# connector.net
KiCad netlist of a schematic drawn in Altium Designer
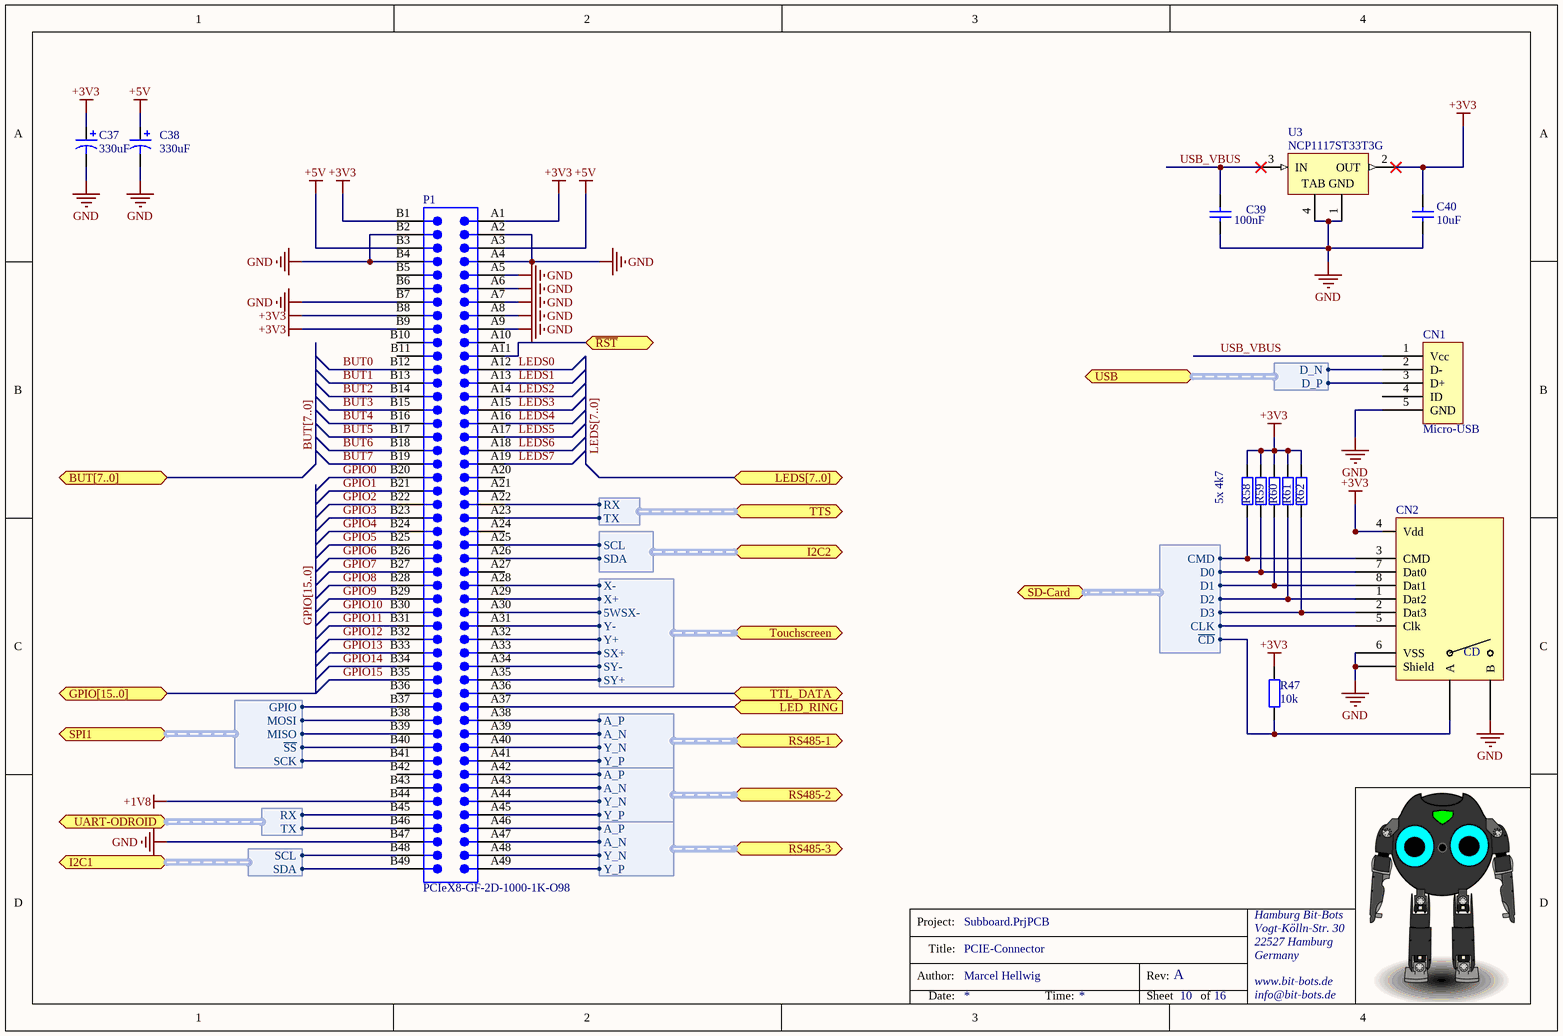
[diagram p0: connector.SchDoc]

(export (version "E")
  (design (tool "Eeschema 10.0.6"))
  (components
    (comp (ref "C37")
      (value "330uF")
      (footprint "Cap 10mm")
      (description "Polarized Capacitor (Radial)")
      (fields
        (field (name "MANUFACTURER") "PANASONIC ELECTRONIC COMPONENTS")
        (field (name "MANUFACTURER PART NUMBER") "EEE1VA331UAP")
        (field (name "PUBLISHER") "Altium Limited")
      )
      (libsource (lib "Miscellaneous Devices") (part "Cap Pol1"))
    )
    (comp (ref "C38")
      (value "330uF")
      (footprint "Cap 10mm")
      (description "Polarized Capacitor (Radial)")
      (fields
        (field (name "MANUFACTURER") "PANASONIC ELECTRONIC COMPONENTS")
        (field (name "MANUFACTURER PART NUMBER") "EEE1VA331UAP")
        (field (name "PUBLISHER") "Altium Limited")
      )
      (libsource (lib "Miscellaneous Devices") (part "Cap Pol1"))
    )
    (comp (ref "C39")
      (value "100nF")
      (footprint "C2012")
      (description "Capacitor")
      (fields
        (field (name "MANUFACTURER") "MULTICOMP")
        (field (name "MANUFACTURER PART NUMBER") "MC0805B104K500CT")
        (field (name "PUBLISHER") "Altium Limited")
      )
      (libsource (lib "Miscellaneous Devices") (part "Cap"))
    )
    (comp (ref "C40")
      (value "10uF")
      (footprint "C2012")
      (description "Capacitor")
      (fields
        (field (name "MANUFACTURER") "MULTICOMP")
        (field (name "MANUFACTURER PART NUMBER") "MC0805X106K250CT")
        (field (name "PUBLISHER") "Altium Limited")
      )
      (libsource (lib "Miscellaneous Devices") (part "Cap"))
    )
    (comp (ref "CN1")
      (value "Micro-USB")
      (footprint "USB-MicroB")
      (fields (field (name "MANUFACTURER") "Molex") (field (name "MANUFACTURER PART NUMBER") "105017-0001"))
      (libsource (lib "bitbots") (part "USB-MicroB"))
    )
    (comp (ref "CN2")
      (value "microSD")
      (footprint "Microsd")
      (description "Micro SD Card Connector")
      (libsource (lib "bitbots") (part "microSD"))
    )
    (comp (ref "P1")
      (value "PCIeX8-GF-2D-1000-1K-O98")
      (footprint "PCIeX8-GF-2D-1000-1K-O98")
      (description "Golden finger, PCIeX8, Dual, Opposite, Pitch 1mm, 98-Position")
      (fields (field (name "PUBLISHER") "Altium"))
      (libsource (lib "Altium Content Vault") (part "CMP-0001-00032-2"))
    )
    (comp (ref "R47")
      (value "10k")
      (footprint "R2012")
      (description "Resistor")
      (fields
        (field (name "MANUFACTURER") "MULTICOMP")
        (field (name "MANUFACTURER PART NUMBER") "MC01W0805110K")
        (field (name "PUBLISHER") "Altium Limited")
      )
      (libsource (lib "") (part "Res2_1"))
    )
    (comp (ref "R58")
      (value "4k7")
      (footprint "R2012")
      (description "Resistor")
      (fields
        (field (name "MANUFACTURER") "MULTICOMP")
        (field (name "MANUFACTURER PART NUMBER") "MC01W080514K7")
        (field (name "PUBLISHER") "Altium Limited")
      )
      (libsource (lib "Miscellaneous Devices") (part "Res2"))
    )
    (comp (ref "R59")
      (value "4k7")
      (footprint "R2012")
      (description "Resistor")
      (fields
        (field (name "MANUFACTURER") "MULTICOMP")
        (field (name "MANUFACTURER PART NUMBER") "MC01W080514K7")
        (field (name "PUBLISHER") "Altium Limited")
      )
      (libsource (lib "Miscellaneous Devices") (part "Res2"))
    )
    (comp (ref "R60")
      (value "4k7")
      (footprint "R2012")
      (description "Resistor")
      (fields
        (field (name "MANUFACTURER") "MULTICOMP")
        (field (name "MANUFACTURER PART NUMBER") "MC01W080514K7")
        (field (name "PUBLISHER") "Altium Limited")
      )
      (libsource (lib "Miscellaneous Devices") (part "Res2"))
    )
    (comp (ref "R61")
      (value "4k7")
      (footprint "R2012")
      (description "Resistor")
      (fields
        (field (name "MANUFACTURER") "MULTICOMP")
        (field (name "MANUFACTURER PART NUMBER") "MC01W080514K7")
        (field (name "PUBLISHER") "Altium Limited")
      )
      (libsource (lib "Miscellaneous Devices") (part "Res2"))
    )
    (comp (ref "R62")
      (value "4k7")
      (footprint "R2012")
      (description "Resistor")
      (fields
        (field (name "MANUFACTURER") "MULTICOMP")
        (field (name "MANUFACTURER PART NUMBER") "MC01W080514K7")
        (field (name "PUBLISHER") "Altium Limited")
      )
      (libsource (lib "Miscellaneous Devices") (part "Res2"))
    )
    (comp (ref "U3")
      (value "NCP1117ST33T3G")
      (footprint "ONSC-SOT-223_L")
      (fields (field (name "PARTNUMBER") "NCP1117ST50T3G") (field (name "MANUFACTURER") "ON Semiconductor"))
      (libsource (lib "Altium Content Vault") (part "CMP-0592-00001-2"))
    )
  )
  (nets
    (net (code "8") (name "+1V8") (class "Default")
      (node (ref "P1") (pin "B44") (pinfunction "B44_B44") (pintype "passive"))
    )
    (net (code "9") (name "+3V3") (class "Default")
      (node (ref "C37") (pin "1") (pinfunction "1_1") (pintype "passive"))
      (node (ref "C40") (pin "2") (pinfunction "2_2") (pintype "passive"))
      (node (ref "CN2") (pin "4") (pinfunction "Vdd_4") (pintype "passive"))
      (node (ref "P1") (pin "A1") (pinfunction "A1_A1") (pintype "passive"))
      (node (ref "P1") (pin "B1") (pinfunction "B1_B1") (pintype "passive"))
      (node (ref "P1") (pin "B8") (pinfunction "B8_B8") (pintype "passive"))
      (node (ref "P1") (pin "B9") (pinfunction "B9_B9") (pintype "passive"))
      (node (ref "R47") (pin "2") (pinfunction "2_2") (pintype "passive"))
      (node (ref "R58") (pin "1") (pinfunction "1_1") (pintype "passive"))
      (node (ref "R59") (pin "1") (pinfunction "1_1") (pintype "passive"))
      (node (ref "R60") (pin "1") (pinfunction "1_1") (pintype "passive"))
      (node (ref "R61") (pin "1") (pinfunction "1_1") (pintype "passive"))
      (node (ref "R62") (pin "1") (pinfunction "1_1") (pintype "passive"))
      (node (ref "U3") (pin "2") (pinfunction "OUT_2") (pintype "output"))
    )
    (net (code "10") (name "+5V") (class "Default")
      (node (ref "C38") (pin "1") (pinfunction "1_1") (pintype "passive"))
      (node (ref "P1") (pin "A3") (pinfunction "A3_A3") (pintype "passive"))
      (node (ref "P1") (pin "B3") (pinfunction "B3_B3") (pintype "passive"))
    )
    (net (code "11") (name "/5WSX-") (class "Default")
      (node (ref "P1") (pin "A30") (pinfunction "A30_A30") (pintype "passive"))
    )
    (net (code "12") (name "/BUT0") (class "Default")
      (node (ref "P1") (pin "B12") (pinfunction "B12_B12") (pintype "passive"))
    )
    (net (code "13") (name "/BUT1") (class "Default")
      (node (ref "P1") (pin "B13") (pinfunction "B13_B13") (pintype "passive"))
    )
    (net (code "14") (name "/BUT2") (class "Default")
      (node (ref "P1") (pin "B14") (pinfunction "B14_B14") (pintype "passive"))
    )
    (net (code "15") (name "/BUT3") (class "Default")
      (node (ref "P1") (pin "B15") (pinfunction "B15_B15") (pintype "passive"))
    )
    (net (code "16") (name "/BUT4") (class "Default")
      (node (ref "P1") (pin "B16") (pinfunction "B16_B16") (pintype "passive"))
    )
    (net (code "17") (name "/BUT5") (class "Default")
      (node (ref "P1") (pin "B17") (pinfunction "B17_B17") (pintype "passive"))
    )
    (net (code "18") (name "/BUT6") (class "Default")
      (node (ref "P1") (pin "B18") (pinfunction "B18_B18") (pintype "passive"))
    )
    (net (code "19") (name "/BUT7") (class "Default")
      (node (ref "P1") (pin "B19") (pinfunction "B19_B19") (pintype "passive"))
    )
    (net (code "21") (name "/CLK") (class "Default")
      (node (ref "CN2") (pin "5") (pinfunction "Clk_5") (pintype "passive"))
    )
    (net (code "22") (name "/CMD") (class "Default")
      (node (ref "CN2") (pin "3") (pinfunction "CMD_3") (pintype "passive"))
      (node (ref "R58") (pin "2") (pinfunction "2_2") (pintype "passive"))
    )
    (net (code "23") (name "/D0") (class "Default")
      (node (ref "CN2") (pin "7") (pinfunction "Dat0_7") (pintype "passive"))
      (node (ref "R59") (pin "2") (pinfunction "2_2") (pintype "passive"))
    )
    (net (code "24") (name "/D1") (class "Default")
      (node (ref "CN2") (pin "8") (pinfunction "Dat1_8") (pintype "passive"))
      (node (ref "R60") (pin "2") (pinfunction "2_2") (pintype "passive"))
    )
    (net (code "25") (name "/D2") (class "Default")
      (node (ref "CN2") (pin "1") (pinfunction "Dat2_1") (pintype "passive"))
      (node (ref "R61") (pin "2") (pinfunction "2_2") (pintype "passive"))
    )
    (net (code "26") (name "/D3") (class "Default")
      (node (ref "CN2") (pin "2") (pinfunction "Dat3_2") (pintype "passive"))
      (node (ref "R62") (pin "2") (pinfunction "2_2") (pintype "passive"))
    )
    (net (code "27") (name "/D_N") (class "Default")
      (node (ref "CN1") (pin "2") (pinfunction "D-_2") (pintype "passive"))
    )
    (net (code "28") (name "/D_P") (class "Default")
      (node (ref "CN1") (pin "3") (pinfunction "D+_3") (pintype "passive"))
    )
    (net (code "29") (name "/GPIO") (class "Default")
      (node (ref "P1") (pin "B37") (pinfunction "B37_B37") (pintype "passive"))
    )
    (net (code "30") (name "/GPIO0") (class "Default")
      (node (ref "P1") (pin "B20") (pinfunction "B20_B20") (pintype "passive"))
    )
    (net (code "31") (name "/GPIO1") (class "Default")
      (node (ref "P1") (pin "B21") (pinfunction "B21_B21") (pintype "passive"))
    )
    (net (code "32") (name "/GPIO2") (class "Default")
      (node (ref "P1") (pin "B22") (pinfunction "B22_B22") (pintype "passive"))
    )
    (net (code "33") (name "/GPIO3") (class "Default")
      (node (ref "P1") (pin "B23") (pinfunction "B23_B23") (pintype "passive"))
    )
    (net (code "34") (name "/GPIO4") (class "Default")
      (node (ref "P1") (pin "B24") (pinfunction "B24_B24") (pintype "passive"))
    )
    (net (code "35") (name "/GPIO5") (class "Default")
      (node (ref "P1") (pin "B25") (pinfunction "B25_B25") (pintype "passive"))
    )
    (net (code "36") (name "/GPIO6") (class "Default")
      (node (ref "P1") (pin "B26") (pinfunction "B26_B26") (pintype "passive"))
    )
    (net (code "37") (name "/GPIO7") (class "Default")
      (node (ref "P1") (pin "B27") (pinfunction "B27_B27") (pintype "passive"))
    )
    (net (code "38") (name "/GPIO8") (class "Default")
      (node (ref "P1") (pin "B28") (pinfunction "B28_B28") (pintype "passive"))
    )
    (net (code "39") (name "/GPIO9") (class "Default")
      (node (ref "P1") (pin "B29") (pinfunction "B29_B29") (pintype "passive"))
    )
    (net (code "40") (name "/GPIO10") (class "Default")
      (node (ref "P1") (pin "B30") (pinfunction "B30_B30") (pintype "passive"))
    )
    (net (code "41") (name "/GPIO11") (class "Default")
      (node (ref "P1") (pin "B31") (pinfunction "B31_B31") (pintype "passive"))
    )
    (net (code "42") (name "/GPIO12") (class "Default")
      (node (ref "P1") (pin "B32") (pinfunction "B32_B32") (pintype "passive"))
    )
    (net (code "43") (name "/GPIO13") (class "Default")
      (node (ref "P1") (pin "B33") (pinfunction "B33_B33") (pintype "passive"))
    )
    (net (code "44") (name "/GPIO14") (class "Default")
      (node (ref "P1") (pin "B34") (pinfunction "B34_B34") (pintype "passive"))
    )
    (net (code "45") (name "/GPIO15") (class "Default")
      (node (ref "P1") (pin "B35") (pinfunction "B35_B35") (pintype "passive"))
    )
    (net (code "47") (name "/LEDS0") (class "Default")
      (node (ref "P1") (pin "A12") (pinfunction "A12_A12") (pintype "passive"))
    )
    (net (code "48") (name "/LEDS1") (class "Default")
      (node (ref "P1") (pin "A13") (pinfunction "A13_A13") (pintype "passive"))
    )
    (net (code "49") (name "/LEDS2") (class "Default")
      (node (ref "P1") (pin "A14") (pinfunction "A14_A14") (pintype "passive"))
    )
    (net (code "50") (name "/LEDS3") (class "Default")
      (node (ref "P1") (pin "A15") (pinfunction "A15_A15") (pintype "passive"))
    )
    (net (code "51") (name "/LEDS4") (class "Default")
      (node (ref "P1") (pin "A16") (pinfunction "A16_A16") (pintype "passive"))
    )
    (net (code "52") (name "/LEDS5") (class "Default")
      (node (ref "P1") (pin "A17") (pinfunction "A17_A17") (pintype "passive"))
    )
    (net (code "53") (name "/LEDS6") (class "Default")
      (node (ref "P1") (pin "A18") (pinfunction "A18_A18") (pintype "passive"))
    )
    (net (code "54") (name "/LEDS7") (class "Default")
      (node (ref "P1") (pin "A19") (pinfunction "A19_A19") (pintype "passive"))
    )
    (net (code "56") (name "/LED_RING") (class "Default")
      (node (ref "P1") (pin "A37") (pinfunction "A37_A37") (pintype "passive"))
    )
    (net (code "57") (name "/MISO") (class "Default")
      (node (ref "P1") (pin "B39") (pinfunction "B39_B39") (pintype "passive"))
    )
    (net (code "58") (name "/MOSI") (class "Default")
      (node (ref "P1") (pin "B38") (pinfunction "B38_B38") (pintype "passive"))
    )
    (net (code "59") (name "/RST") (class "Default")
      (node (ref "P1") (pin "A11") (pinfunction "A11_A11") (pintype "passive"))
    )
    (net (code "60") (name "/SCK") (class "Default")
      (node (ref "P1") (pin "B41") (pinfunction "B41_B41") (pintype "passive"))
    )
    (net (code "61") (name "/SX+") (class "Default")
      (node (ref "P1") (pin "A33") (pinfunction "A33_A33") (pintype "passive"))
    )
    (net (code "62") (name "/SY+") (class "Default")
      (node (ref "P1") (pin "A35") (pinfunction "A35_A35") (pintype "passive"))
    )
    (net (code "63") (name "/SY-") (class "Default")
      (node (ref "P1") (pin "A34") (pinfunction "A34_A34") (pintype "passive"))
    )
    (net (code "64") (name "/TTL_DATA") (class "Default")
      (node (ref "P1") (pin "A36") (pinfunction "A36_A36") (pintype "passive"))
    )
    (net (code "65") (name "/USB_VBUS") (class "Default")
      (node (ref "C39") (pin "2") (pinfunction "2_2") (pintype "passive"))
      (node (ref "CN1") (pin "1") (pinfunction "Vcc_1") (pintype "power_in"))
      (node (ref "U3") (pin "3") (pinfunction "IN_3") (pintype "input"))
    )
    (net (code "66") (name "/X+") (class "Default")
      (node (ref "P1") (pin "A29") (pinfunction "A29_A29") (pintype "passive"))
    )
    (net (code "67") (name "/X-") (class "Default")
      (node (ref "P1") (pin "A28") (pinfunction "A28_A28") (pintype "passive"))
    )
    (net (code "68") (name "/Y+") (class "Default")
      (node (ref "P1") (pin "A32") (pinfunction "A32_A32") (pintype "passive"))
    )
    (net (code "69") (name "/Y-") (class "Default")
      (node (ref "P1") (pin "A31") (pinfunction "A31_A31") (pintype "passive"))
    )
    (net (code "77") (name "/~{CD}") (class "Default")
      (node (ref "CN2") (pin "A") (pinfunction "A_A") (pintype "passive"))
      (node (ref "R47") (pin "1") (pinfunction "1_1") (pintype "passive"))
    )
    (net (code "78") (name "/~{SS}") (class "Default")
      (node (ref "P1") (pin "B40") (pinfunction "B40_B40") (pintype "passive"))
    )
    (net (code "79") (name "GND") (class "Default")
      (node (ref "C37") (pin "2") (pinfunction "2_2") (pintype "passive"))
      (node (ref "C38") (pin "2") (pinfunction "2_2") (pintype "passive"))
      (node (ref "C39") (pin "1") (pinfunction "1_1") (pintype "passive"))
      (node (ref "C40") (pin "1") (pinfunction "1_1") (pintype "passive"))
      (node (ref "CN1") (pin "5") (pinfunction "GND_5") (pintype "power_in"))
      (node (ref "CN2") (pin "6") (pinfunction "VSS_6") (pintype "passive"))
      (node (ref "CN2") (pin "B") (pinfunction "B_B") (pintype "passive"))
      (node (ref "CN2") (pin "sh") (pinfunction "Shield_sh") (pintype "passive"))
      (node (ref "P1") (pin "A2") (pinfunction "A2_A2") (pintype "passive"))
      (node (ref "P1") (pin "A4") (pinfunction "A4_A4") (pintype "passive"))
      (node (ref "P1") (pin "A5") (pinfunction "A5_A5") (pintype "passive"))
      (node (ref "P1") (pin "A6") (pinfunction "A6_A6") (pintype "passive"))
      (node (ref "P1") (pin "A7") (pinfunction "A7_A7") (pintype "passive"))
      (node (ref "P1") (pin "A8") (pinfunction "A8_A8") (pintype "passive"))
      (node (ref "P1") (pin "A9") (pinfunction "A9_A9") (pintype "passive"))
      (node (ref "P1") (pin "B2") (pinfunction "B2_B2") (pintype "passive"))
      (node (ref "P1") (pin "B4") (pinfunction "B4_B4") (pintype "passive"))
      (node (ref "P1") (pin "B47") (pinfunction "B47_B47") (pintype "passive"))
      (node (ref "P1") (pin "B7") (pinfunction "B7_B7") (pintype "passive"))
      (node (ref "U3") (pin "1") (pinfunction "GND_1") (pintype "power_in"))
      (node (ref "U3") (pin "4") (pinfunction "TAB_4") (pintype "power_in"))
    )
    (net (code "80") (name "unconnected-(CN1-ID-Pad4)") (class "Default")
      (node (ref "CN1") (pin "4") (pinfunction "ID_4") (pintype "passive"))
    )
    (net (code "81") (name "unconnected-(P1-PadA10)") (class "Default")
      (node (ref "P1") (pin "A10") (pinfunction "A10_A10") (pintype "passive"))
    )
    (net (code "82") (name "unconnected-(P1-PadA20)") (class "Default")
      (node (ref "P1") (pin "A20") (pinfunction "A20_A20") (pintype "passive"))
    )
    (net (code "83") (name "unconnected-(P1-PadA21)") (class "Default")
      (node (ref "P1") (pin "A21") (pinfunction "A21_A21") (pintype "passive"))
    )
    (net (code "84") (name "unconnected-(P1-PadA22)") (class "Default")
      (node (ref "P1") (pin "A22") (pinfunction "A22_A22") (pintype "passive"))
    )
    (net (code "85") (name "unconnected-(P1-PadA23)") (class "Default")
      (node (ref "P1") (pin "A23") (pinfunction "A23_A23") (pintype "passive"))
    )
    (net (code "86") (name "unconnected-(P1-PadA24)") (class "Default")
      (node (ref "P1") (pin "A24") (pinfunction "A24_A24") (pintype "passive"))
    )
    (net (code "87") (name "unconnected-(P1-PadA25)") (class "Default")
      (node (ref "P1") (pin "A25") (pinfunction "A25_A25") (pintype "passive"))
    )
    (net (code "88") (name "unconnected-(P1-PadA26)") (class "Default")
      (node (ref "P1") (pin "A26") (pinfunction "A26_A26") (pintype "passive"))
    )
    (net (code "89") (name "unconnected-(P1-PadA27)") (class "Default")
      (node (ref "P1") (pin "A27") (pinfunction "A27_A27") (pintype "passive"))
    )
    (net (code "90") (name "unconnected-(P1-PadA38)") (class "Default")
      (node (ref "P1") (pin "A38") (pinfunction "A38_A38") (pintype "passive"))
    )
    (net (code "91") (name "unconnected-(P1-PadA39)") (class "Default")
      (node (ref "P1") (pin "A39") (pinfunction "A39_A39") (pintype "passive"))
    )
    (net (code "92") (name "unconnected-(P1-PadA40)") (class "Default")
      (node (ref "P1") (pin "A40") (pinfunction "A40_A40") (pintype "passive"))
    )
    (net (code "93") (name "unconnected-(P1-PadA41)") (class "Default")
      (node (ref "P1") (pin "A41") (pinfunction "A41_A41") (pintype "passive"))
    )
    (net (code "94") (name "unconnected-(P1-PadA42)") (class "Default")
      (node (ref "P1") (pin "A42") (pinfunction "A42_A42") (pintype "passive"))
    )
    (net (code "95") (name "unconnected-(P1-PadA43)") (class "Default")
      (node (ref "P1") (pin "A43") (pinfunction "A43_A43") (pintype "passive"))
    )
    (net (code "96") (name "unconnected-(P1-PadA44)") (class "Default")
      (node (ref "P1") (pin "A44") (pinfunction "A44_A44") (pintype "passive"))
    )
    (net (code "97") (name "unconnected-(P1-PadA45)") (class "Default")
      (node (ref "P1") (pin "A45") (pinfunction "A45_A45") (pintype "passive"))
    )
    (net (code "98") (name "unconnected-(P1-PadA46)") (class "Default")
      (node (ref "P1") (pin "A46") (pinfunction "A46_A46") (pintype "passive"))
    )
    (net (code "99") (name "unconnected-(P1-PadA47)") (class "Default")
      (node (ref "P1") (pin "A47") (pinfunction "A47_A47") (pintype "passive"))
    )
    (net (code "100") (name "unconnected-(P1-PadA48)") (class "Default")
      (node (ref "P1") (pin "A48") (pinfunction "A48_A48") (pintype "passive"))
    )
    (net (code "101") (name "unconnected-(P1-PadA49)") (class "Default")
      (node (ref "P1") (pin "A49") (pinfunction "A49_A49") (pintype "passive"))
    )
    (net (code "102") (name "unconnected-(P1-PadB5)") (class "Default")
      (node (ref "P1") (pin "B5") (pinfunction "B5_B5") (pintype "passive"))
    )
    (net (code "103") (name "unconnected-(P1-PadB6)") (class "Default")
      (node (ref "P1") (pin "B6") (pinfunction "B6_B6") (pintype "passive"))
    )
    (net (code "104") (name "unconnected-(P1-PadB10)") (class "Default")
      (node (ref "P1") (pin "B10") (pinfunction "B10_B10") (pintype "passive"))
    )
    (net (code "105") (name "unconnected-(P1-PadB11)") (class "Default")
      (node (ref "P1") (pin "B11") (pinfunction "B11_B11") (pintype "passive"))
    )
    (net (code "106") (name "unconnected-(P1-PadB36)") (class "Default")
      (node (ref "P1") (pin "B36") (pinfunction "B36_B36") (pintype "passive"))
    )
    (net (code "107") (name "unconnected-(P1-PadB42)") (class "Default")
      (node (ref "P1") (pin "B42") (pinfunction "B42_B42") (pintype "passive"))
    )
    (net (code "108") (name "unconnected-(P1-PadB43)") (class "Default")
      (node (ref "P1") (pin "B43") (pinfunction "B43_B43") (pintype "passive"))
    )
    (net (code "109") (name "unconnected-(P1-PadB45)") (class "Default")
      (node (ref "P1") (pin "B45") (pinfunction "B45_B45") (pintype "passive"))
    )
    (net (code "110") (name "unconnected-(P1-PadB46)") (class "Default")
      (node (ref "P1") (pin "B46") (pinfunction "B46_B46") (pintype "passive"))
    )
    (net (code "111") (name "unconnected-(P1-PadB48)") (class "Default")
      (node (ref "P1") (pin "B48") (pinfunction "B48_B48") (pintype "passive"))
    )
    (net (code "112") (name "unconnected-(P1-PadB49)") (class "Default")
      (node (ref "P1") (pin "B49") (pinfunction "B49_B49") (pintype "passive"))
    )
  )
)
